# audio-connectors.net
KiCad netlist of a schematic drawn in Altium Designer
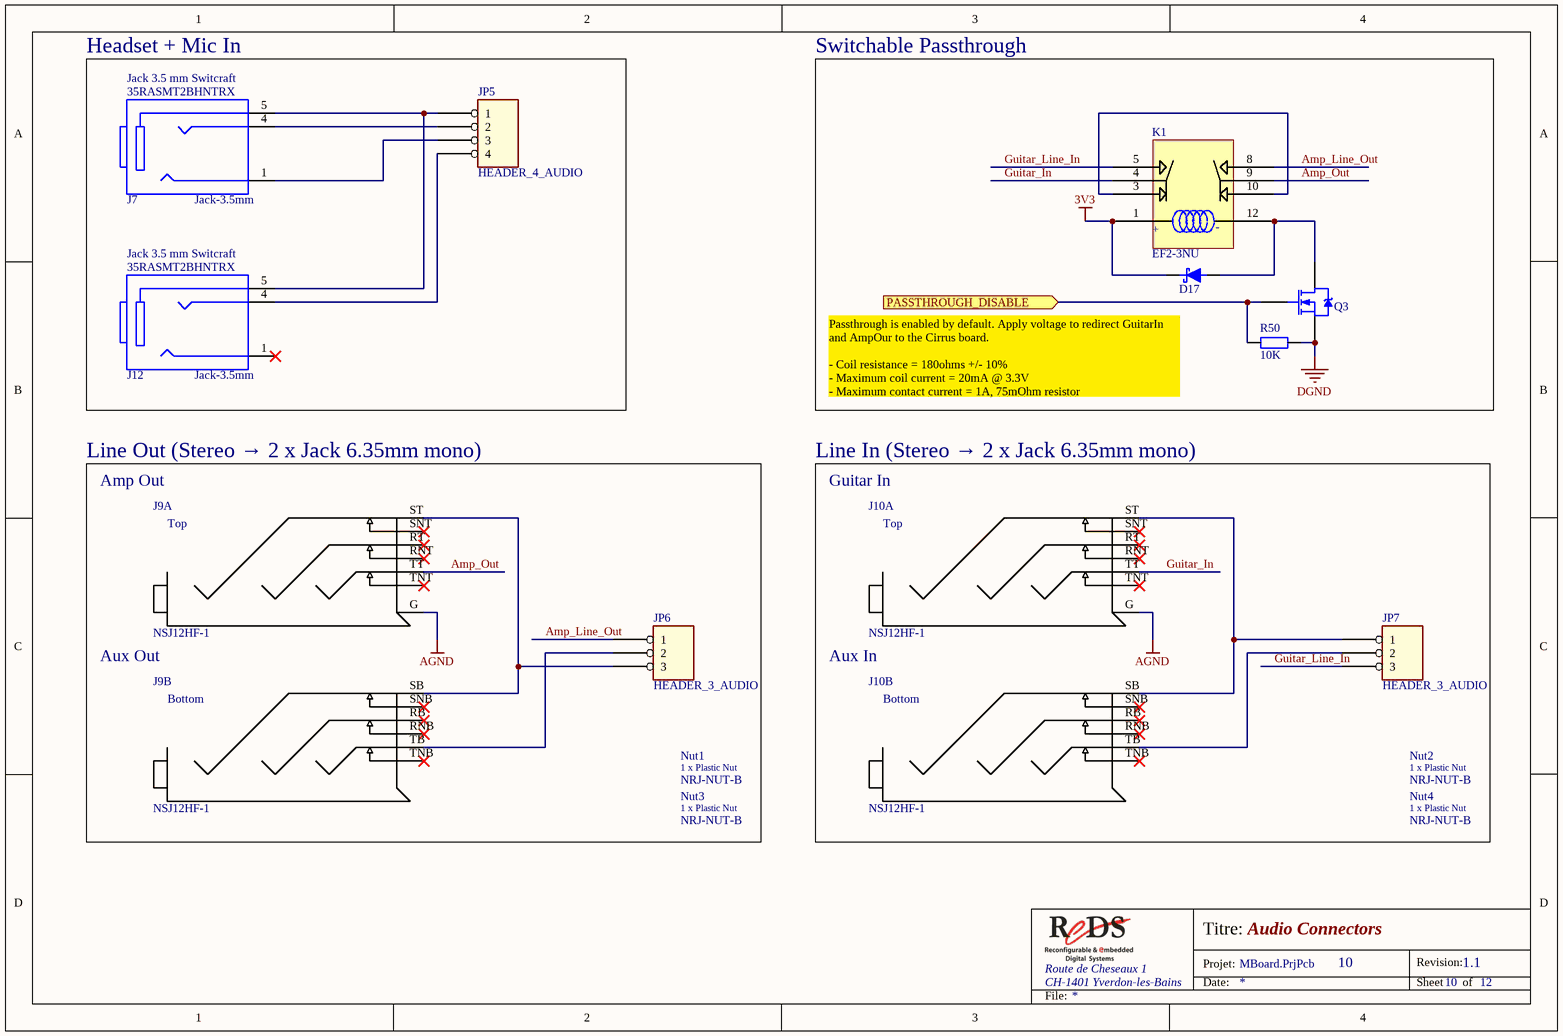
[diagram p0: audio-connectors.SchDoc]

(export (version "E")
  (design (tool "Eeschema 10.0.6"))
  (components
    (comp (ref "D17")
      (value "B340A")
      (footprint "SM/D_DO214-AC (SMA)")
      (description "DIODE SCHOTTKY 30V 3A SMA")
      (libsource (lib "MBoard") (part "Diode Schottky B340A"))
    )
    (comp (ref "J7")
      (value "Jack-3.5mm")
      (footprint "CON_JACK_3.5MM_SMD_Switchcraft_35RASMT2BHNTRX")
      (description "Connecteur Jack 3.5mm")
      (fields (field (name "MANUFACTURER") "Switchcraft"))
      (libsource (lib "Database_heig-vd") (part "Jack 3.5 Switchcraft 35RASMT2BHNTRX"))
    )
    (comp (ref "J9")
      (value "NSJ12HF-1")
      (footprint "NSJ12HF-1")
      (description "Neutronik 2xJack 6.35 connector")
      (libsource (lib "MBoard") (part "Jack 6.35 NSJ12HF-1"))
    )
    (comp (ref "J10")
      (value "NSJ12HF-1")
      (footprint "NSJ12HF-1")
      (description "Neutronik 2xJack 6.35 connector")
      (libsource (lib "MBoard") (part "Jack 6.35 NSJ12HF-1"))
    )
    (comp (ref "J12")
      (value "Jack-3.5mm")
      (footprint "CON_JACK_3.5MM_SMD_Switchcraft_35RASMT2BHNTRX")
      (description "Connecteur Jack 3.5mm")
      (fields (field (name "MANUFACTURER") "Switchcraft"))
      (libsource (lib "Database_heig-vd") (part "Jack 3.5 Switchcraft 35RASMT2BHNTRX"))
    )
    (comp (ref "JP5")
      (value "HEADER_4_AUDIO")
      (footprint "HEADER4_WIRE")
      (fields (field (name "MANUFACTURER") "REDS"))
      (libsource (lib "MBoard") (part "HEADER_4_AUDIO"))
    )
    (comp (ref "JP6")
      (value "HEADER_3_AUDIO")
      (footprint "HEADER3_WIRE")
      (fields (field (name "MANUFACTURER") "REDS"))
      (libsource (lib "MBoard") (part "HEADER_3_AUDIO"))
    )
    (comp (ref "JP7")
      (value "HEADER_3_AUDIO")
      (footprint "HEADER3_WIRE")
      (fields (field (name "MANUFACTURER") "REDS"))
      (libsource (lib "MBoard") (part "HEADER_3_AUDIO"))
    )
    (comp (ref "K1")
      (value "EF2-3NU")
      (footprint "EF2-NU")
      (description "Miniature Signal Relay")
      (libsource (lib "MBoard") (part "EF2-3NU"))
    )
    (comp (ref "Nut1")
      (value "NRJ-NUT-B")
      (description "Plastic Nut to fasten 6.35 jack")
      (fields (field (name "MANUFACTURER") "Neutrik"))
      (libsource (lib "MBoard") (part "Jack 6.35 Plastic Nut"))
    )
    (comp (ref "Nut2")
      (value "NRJ-NUT-B")
      (description "Plastic Nut to fasten 6.35 jack")
      (fields (field (name "MANUFACTURER") "Neutrik"))
      (libsource (lib "MBoard") (part "Jack 6.35 Plastic Nut"))
    )
    (comp (ref "Nut3")
      (value "NRJ-NUT-B")
      (description "Plastic Nut to fasten 6.35 jack")
      (fields (field (name "MANUFACTURER") "Neutrik"))
      (libsource (lib "MBoard") (part "Jack 6.35 Plastic Nut"))
    )
    (comp (ref "Nut4")
      (value "NRJ-NUT-B")
      (description "Plastic Nut to fasten 6.35 jack")
      (fields (field (name "MANUFACTURER") "Neutrik"))
      (libsource (lib "MBoard") (part "Jack 6.35 Plastic Nut"))
    )
    (comp (ref "Q3")
      (value "FDV301N")
      (footprint "SOT23")
      (description "MOSFET N-CH 25V 220MA SOT-23")
      (fields (field (name "MANUFACTURER") "Fairchild Semiconductor"))
      (libsource (lib "Database_heig-vd") (part "Transistor MOSFET N/GSD"))
    )
    (comp (ref "R50")
      (value "10K")
      (footprint "SM/R_0603")
      (description "Résistance 0603 63mW 1% 10K")
      (fields (field (name "MANUFACTURER") "Multicomp") (field (name "POWER") "63mW"))
      (libsource (lib "Database_heig-vd") (part "Res"))
    )
  )
  (nets
    (net (code "1") (name "/Amp_Line_Out") (class "Default")
      (node (ref "JP6") (pin "1") (pinfunction "1_1") (pintype "passive"))
      (node (ref "K1") (pin "8") (pinfunction "8_8") (pintype "passive"))
    )
    (net (code "2") (name "/Amp_Out") (class "Default")
      (node (ref "J9") (pin "TT") (pintype "passive"))
      (node (ref "K1") (pin "9") (pinfunction "9_9") (pintype "passive"))
    )
    (net (code "3") (name "/Guitar_In") (class "Default")
      (node (ref "J10") (pin "TT") (pintype "passive"))
      (node (ref "K1") (pin "4") (pinfunction "4_4") (pintype "passive"))
    )
    (net (code "4") (name "/Guitar_Line_In") (class "Default")
      (node (ref "JP7") (pin "3") (pinfunction "3_3") (pintype "passive"))
      (node (ref "K1") (pin "5") (pinfunction "5_5") (pintype "passive"))
    )
    (net (code "5") (name "/PASSTHROUGH_DISABLE") (class "Default")
      (node (ref "Q3") (pin "1") (pinfunction "G_1") (pintype "passive"))
      (node (ref "R50") (pin "1") (pinfunction "1_1") (pintype "passive"))
    )
    (net (code "6") (name "3V3") (class "Default")
      (node (ref "D17") (pin "2") (pinfunction "C_2") (pintype "passive"))
      (node (ref "K1") (pin "1") (pinfunction "1_1") (pintype "passive"))
    )
    (net (code "7") (name "AGND") (class "Default")
      (node (ref "J10") (pin "G") (pinfunction "G_G") (pintype "passive"))
      (node (ref "J9") (pin "G") (pinfunction "G_G") (pintype "passive"))
    )
    (net (code "8") (name "DGND") (class "Default")
      (node (ref "Q3") (pin "2") (pinfunction "S_2") (pintype "passive"))
      (node (ref "R50") (pin "2") (pinfunction "2_2") (pintype "passive"))
    )
    (net (code "9") (name "Net-(D17-A)") (class "Default")
      (node (ref "D17") (pin "1") (pinfunction "A_1") (pintype "passive"))
      (node (ref "K1") (pin "12") (pinfunction "12_12") (pintype "passive"))
      (node (ref "Q3") (pin "3") (pinfunction "D_3") (pintype "passive"))
    )
    (net (code "10") (name "Net-(J7-Pad1)") (class "Default")
      (node (ref "J7") (pin "1") (pinfunction "1_1") (pintype "passive"))
      (node (ref "JP5") (pin "3") (pinfunction "3_3") (pintype "passive"))
    )
    (net (code "11") (name "Net-(J7-Pad4)") (class "Default")
      (node (ref "J7") (pin "4") (pinfunction "4_4") (pintype "passive"))
      (node (ref "JP5") (pin "2") (pinfunction "2_2") (pintype "passive"))
    )
    (net (code "12") (name "Net-(J9-PadSB)") (class "Default")
      (node (ref "J9") (pin "SB") (pintype "passive"))
      (node (ref "J9") (pin "ST") (pintype "passive"))
      (node (ref "JP6") (pin "3") (pinfunction "3_3") (pintype "passive"))
    )
    (net (code "13") (name "Net-(J9-PadTB)") (class "Default")
      (node (ref "J9") (pin "TB") (pintype "passive"))
      (node (ref "JP6") (pin "2") (pinfunction "2_2") (pintype "passive"))
    )
    (net (code "14") (name "Net-(J10-PadSB)") (class "Default")
      (node (ref "J10") (pin "SB") (pintype "passive"))
      (node (ref "J10") (pin "ST") (pintype "passive"))
      (node (ref "JP7") (pin "1") (pinfunction "1_1") (pintype "passive"))
    )
    (net (code "15") (name "Net-(J10-PadTB)") (class "Default")
      (node (ref "J10") (pin "TB") (pintype "passive"))
      (node (ref "JP7") (pin "2") (pinfunction "2_2") (pintype "passive"))
    )
    (net (code "16") (name "Net-(J12-5-GND)") (class "Default")
      (node (ref "J12") (pin "5") (pinfunction "5-GND_5") (pintype "passive"))
      (node (ref "J7") (pin "5") (pinfunction "5-GND_5") (pintype "passive"))
      (node (ref "JP5") (pin "1") (pinfunction "1_1") (pintype "passive"))
    )
    (net (code "17") (name "Net-(J12-Pad4)") (class "Default")
      (node (ref "J12") (pin "4") (pinfunction "4_4") (pintype "passive"))
      (node (ref "JP5") (pin "4") (pinfunction "4_4") (pintype "passive"))
    )
    (net (code "18") (name "Net-(K1-Pad10)") (class "Default")
      (node (ref "K1") (pin "10") (pinfunction "10_10") (pintype "passive"))
      (node (ref "K1") (pin "3") (pinfunction "3_3") (pintype "passive"))
    )
    (net (code "19") (name "unconnected-(J9-PadRB)") (class "Default")
      (node (ref "J9") (pin "RB") (pintype "passive+no_connect"))
    )
    (net (code "20") (name "unconnected-(J9-PadRNB)") (class "Default")
      (node (ref "J9") (pin "RNB") (pintype "passive+no_connect"))
    )
    (net (code "21") (name "unconnected-(J9-PadRNT)") (class "Default")
      (node (ref "J9") (pin "RNT") (pintype "passive+no_connect"))
    )
    (net (code "22") (name "unconnected-(J9-PadRT)") (class "Default")
      (node (ref "J9") (pin "RT") (pintype "passive+no_connect"))
    )
    (net (code "23") (name "unconnected-(J9-PadSNB)") (class "Default")
      (node (ref "J9") (pin "SNB") (pintype "passive+no_connect"))
    )
    (net (code "24") (name "unconnected-(J9-PadSNT)") (class "Default")
      (node (ref "J9") (pin "SNT") (pintype "passive+no_connect"))
    )
    (net (code "25") (name "unconnected-(J9-PadTNB)") (class "Default")
      (node (ref "J9") (pin "TNB") (pintype "passive+no_connect"))
    )
    (net (code "26") (name "unconnected-(J9-PadTNT)") (class "Default")
      (node (ref "J9") (pin "TNT") (pintype "passive+no_connect"))
    )
    (net (code "27") (name "unconnected-(J10-PadRB)") (class "Default")
      (node (ref "J10") (pin "RB") (pintype "passive+no_connect"))
    )
    (net (code "28") (name "unconnected-(J10-PadRNB)") (class "Default")
      (node (ref "J10") (pin "RNB") (pintype "passive+no_connect"))
    )
    (net (code "29") (name "unconnected-(J10-PadRNT)") (class "Default")
      (node (ref "J10") (pin "RNT") (pintype "passive+no_connect"))
    )
    (net (code "30") (name "unconnected-(J10-PadRT)") (class "Default")
      (node (ref "J10") (pin "RT") (pintype "passive+no_connect"))
    )
    (net (code "31") (name "unconnected-(J10-PadSNB)") (class "Default")
      (node (ref "J10") (pin "SNB") (pintype "passive+no_connect"))
    )
    (net (code "32") (name "unconnected-(J10-PadSNT)") (class "Default")
      (node (ref "J10") (pin "SNT") (pintype "passive+no_connect"))
    )
    (net (code "33") (name "unconnected-(J10-PadTNB)") (class "Default")
      (node (ref "J10") (pin "TNB") (pintype "passive+no_connect"))
    )
    (net (code "34") (name "unconnected-(J10-PadTNT)") (class "Default")
      (node (ref "J10") (pin "TNT") (pintype "passive+no_connect"))
    )
    (net (code "35") (name "unconnected-(J12-Pad1)") (class "Default")
      (node (ref "J12") (pin "1") (pinfunction "1_1") (pintype "passive+no_connect"))
    )
  )
)
